# madaq_filter_panel.net
KiCad netlist of a schematic drawn in EAGLE
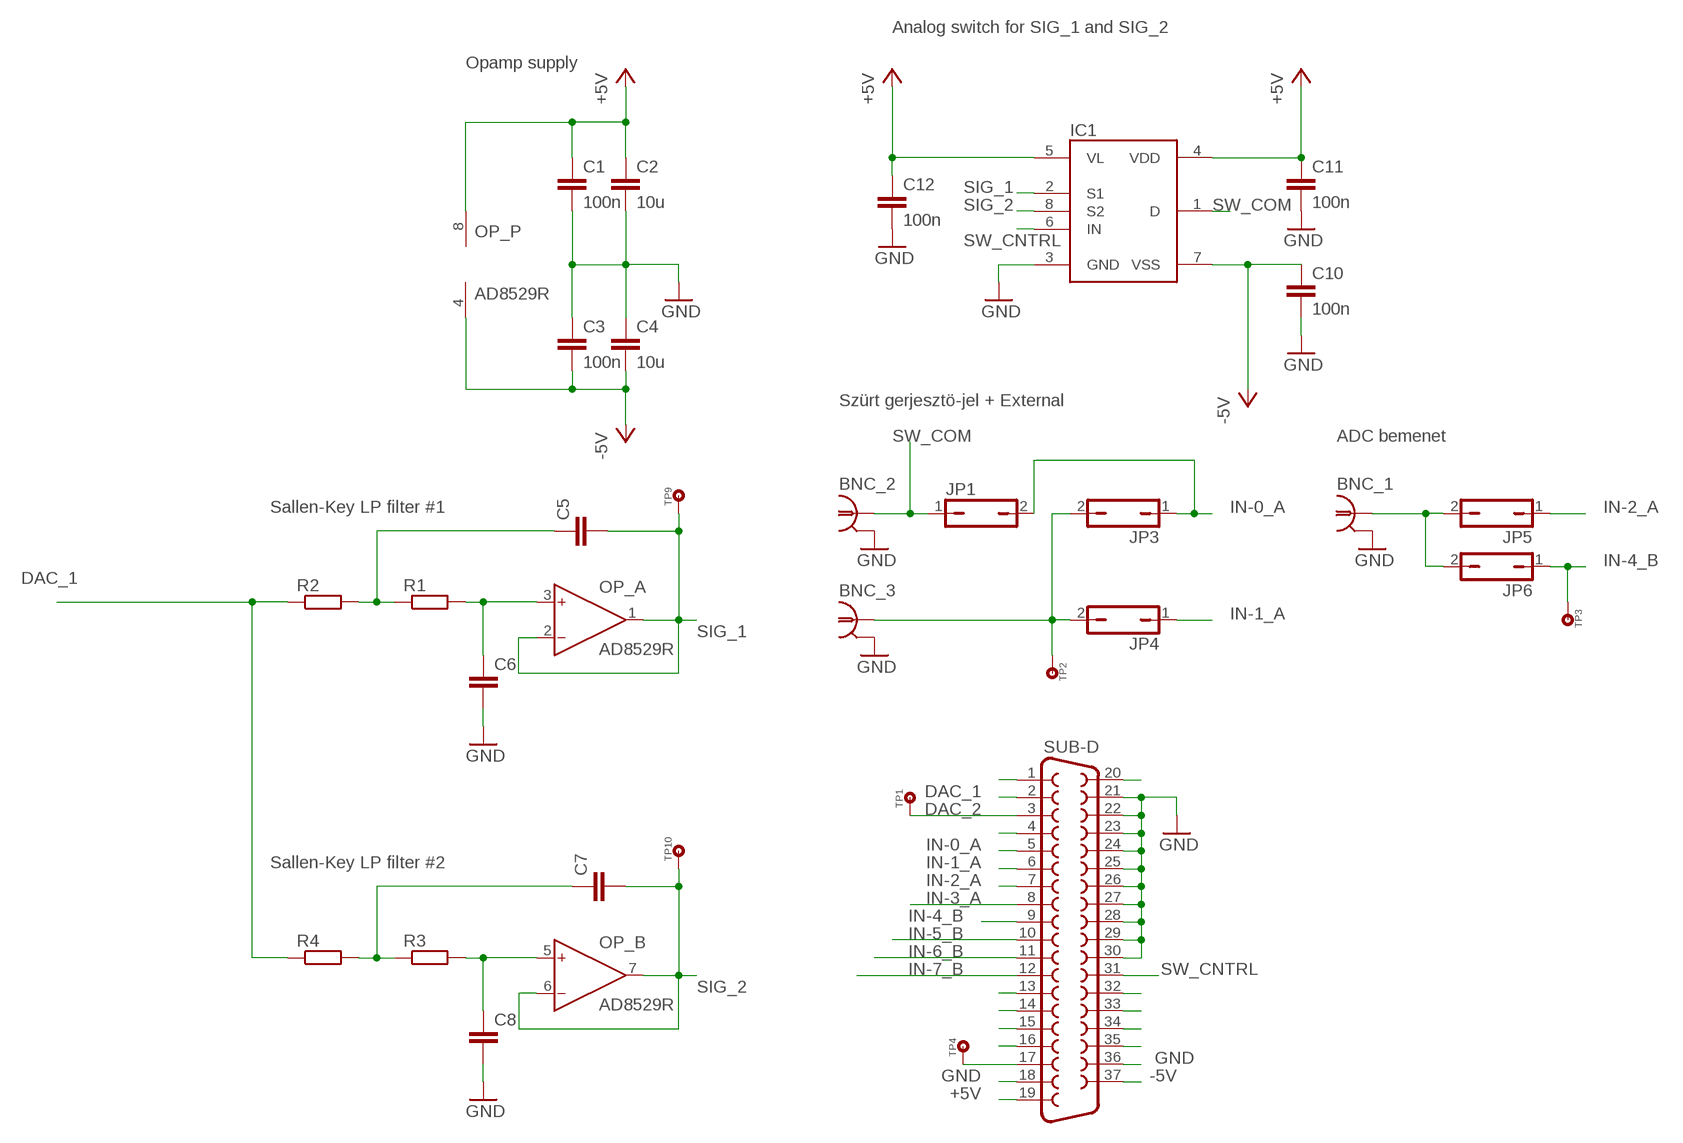
[diagram p0: schematic, sheet 1]

(export (version "E")
  (design (tool "Eeschema 10.0.6"))
  (components
    (comp (ref "BNC_1")
      (value "BNC-ISOL-90I")
      (footprint "eagle-import:BNCPCB90I")
      (libsource (lib "eagle-import") (part "BNC-ISOL-90I"))
    )
    (comp (ref "BNC_2")
      (value "BNC-ISOL-90I")
      (footprint "eagle-import:BNCPCB90I")
      (libsource (lib "eagle-import") (part "BNC-ISOL-90I"))
    )
    (comp (ref "BNC_3")
      (value "BNC-ISOL-90I")
      (footprint "eagle-import:BNCPCB90I")
      (libsource (lib "eagle-import") (part "BNC-ISOL-90I"))
    )
    (comp (ref "C1")
      (value "100n")
      (footprint "eagle-import:C1206")
      (libsource (lib "eagle-import") (part "C1206"))
    )
    (comp (ref "C2")
      (value "10u")
      (footprint "eagle-import:C1206")
      (libsource (lib "eagle-import") (part "C1206"))
    )
    (comp (ref "C3")
      (value "100n")
      (footprint "eagle-import:C1206")
      (libsource (lib "eagle-import") (part "C1206"))
    )
    (comp (ref "C4")
      (value "10u")
      (footprint "eagle-import:C1206")
      (libsource (lib "eagle-import") (part "C1206"))
    )
    (comp (ref "C5")
      (value "C1206")
      (footprint "eagle-import:C1206")
      (libsource (lib "eagle-import") (part "C1206"))
    )
    (comp (ref "C6")
      (value "C1206")
      (footprint "eagle-import:C1206")
      (libsource (lib "eagle-import") (part "C1206"))
    )
    (comp (ref "C7")
      (value "C1206")
      (footprint "eagle-import:C1206")
      (libsource (lib "eagle-import") (part "C1206"))
    )
    (comp (ref "C8")
      (value "C1206")
      (footprint "eagle-import:C1206")
      (libsource (lib "eagle-import") (part "C1206"))
    )
    (comp (ref "C10")
      (value "100n")
      (footprint "eagle-import:C1206")
      (libsource (lib "eagle-import") (part "C1206"))
    )
    (comp (ref "C11")
      (value "100n")
      (footprint "eagle-import:C1206")
      (libsource (lib "eagle-import") (part "C1206"))
    )
    (comp (ref "C12")
      (value "100n")
      (footprint "eagle-import:C1206")
      (libsource (lib "eagle-import") (part "C1206"))
    )
    (comp (ref "IC1")
      (value "ADG419BR")
      (footprint "eagle-import:SO08")
      (libsource (lib "eagle-import") (part "ADG419BR"))
    )
    (comp (ref "JP1")
      (value "JP1Q")
      (footprint "eagle-import:JP1")
      (libsource (lib "eagle-import") (part "JP1Q"))
    )
    (comp (ref "JP3")
      (value "JP1Q")
      (footprint "eagle-import:JP1")
      (libsource (lib "eagle-import") (part "JP1Q"))
    )
    (comp (ref "JP4")
      (value "JP1Q")
      (footprint "eagle-import:JP1")
      (libsource (lib "eagle-import") (part "JP1Q"))
    )
    (comp (ref "JP5")
      (value "JP1Q")
      (footprint "eagle-import:JP1")
      (libsource (lib "eagle-import") (part "JP1Q"))
    )
    (comp (ref "JP6")
      (value "JP1Q")
      (footprint "eagle-import:JP1")
      (libsource (lib "eagle-import") (part "JP1Q"))
    )
    (comp (ref "OP_")
      (value "AD8529R")
      (footprint "eagle-import:SO8")
      (fields (field (name "MF") "ALTERA CORPORATION") (field (name "MPN") "AD8529ARZ"))
      (libsource (lib "eagle-import") (part "AD8529R"))
    )
    (comp (ref "R1")
      (value "R1206")
      (footprint "eagle-import:R1206")
      (libsource (lib "eagle-import") (part "R1206"))
    )
    (comp (ref "R2")
      (value "R1206")
      (footprint "eagle-import:R1206")
      (libsource (lib "eagle-import") (part "R1206"))
    )
    (comp (ref "R3")
      (value "R1206")
      (footprint "eagle-import:R1206")
      (libsource (lib "eagle-import") (part "R1206"))
    )
    (comp (ref "R4")
      (value "R1206")
      (footprint "eagle-import:R1206")
      (libsource (lib "eagle-import") (part "R1206"))
    )
    (comp (ref "SUB-D")
      (value "F37HP")
      (footprint "eagle-import:F37HP")
      (libsource (lib "eagle-import") (part "F37HP"))
    )
    (comp (ref "TP1")
      (value "TP")
      (footprint "eagle-import:JP1")
      (libsource (lib "eagle-import") (part "TP"))
    )
    (comp (ref "TP2")
      (value "TP")
      (footprint "eagle-import:JP1")
      (libsource (lib "eagle-import") (part "TP"))
    )
    (comp (ref "TP3")
      (value "TP")
      (footprint "eagle-import:JP1")
      (libsource (lib "eagle-import") (part "TP"))
    )
    (comp (ref "TP4")
      (value "TP")
      (footprint "eagle-import:JP1")
      (libsource (lib "eagle-import") (part "TP"))
    )
    (comp (ref "TP9")
      (value "TP")
      (footprint "eagle-import:JP1")
      (libsource (lib "eagle-import") (part "TP"))
    )
    (comp (ref "TP10")
      (value "TP")
      (footprint "eagle-import:JP1")
      (libsource (lib "eagle-import") (part "TP"))
    )
  )
  (nets
    (net (code "1") (name "+5V") (class "Default")
      (node (ref "C1") (pin "2") (pinfunction "2_2") (pintype "passive"))
      (node (ref "C11") (pin "2") (pinfunction "2_2") (pintype "passive"))
      (node (ref "C12") (pin "2") (pinfunction "2_2") (pintype "passive"))
      (node (ref "C2") (pin "2") (pinfunction "2_2") (pintype "passive"))
      (node (ref "IC1") (pin "4") (pinfunction "VDD_4") (pintype "power_in"))
      (node (ref "IC1") (pin "5") (pinfunction "VL_5") (pintype "power_in"))
      (node (ref "OP_") (pin "8") (pinfunction "V+_8") (pintype "power_in"))
      (node (ref "SUB-D") (pin "19") (pinfunction "19_19") (pintype "passive"))
    )
    (net (code "2") (name "-5V") (class "Default")
      (node (ref "C10") (pin "2") (pinfunction "2_2") (pintype "passive"))
      (node (ref "C3") (pin "1") (pinfunction "1_1") (pintype "passive"))
      (node (ref "C4") (pin "1") (pinfunction "1_1") (pintype "passive"))
      (node (ref "IC1") (pin "7") (pinfunction "VSS_7") (pintype "power_in"))
      (node (ref "OP_") (pin "4") (pinfunction "V-_4") (pintype "power_in"))
      (node (ref "SUB-D") (pin "37") (pinfunction "37_37") (pintype "passive"))
    )
    (net (code "3") (name "/DAC_1") (class "Default")
      (node (ref "R2") (pin "1") (pinfunction "1_1") (pintype "passive"))
      (node (ref "R4") (pin "1") (pinfunction "1_1") (pintype "passive"))
      (node (ref "SUB-D") (pin "2") (pinfunction "2_2") (pintype "passive"))
    )
    (net (code "4") (name "/DAC_2") (class "Default")
      (node (ref "SUB-D") (pin "3") (pinfunction "3_3") (pintype "passive"))
      (node (ref "TP1") (pin "1") (pinfunction "1_1") (pintype "bidirectional"))
    )
    (net (code "5") (name "/IN-0_A") (class "Default")
      (node (ref "JP1") (pin "2") (pinfunction "2_2") (pintype "passive"))
      (node (ref "JP3") (pin "1") (pinfunction "1_1") (pintype "passive"))
      (node (ref "SUB-D") (pin "5") (pinfunction "5_5") (pintype "passive"))
    )
    (net (code "6") (name "/IN-1_A") (class "Default")
      (node (ref "JP4") (pin "1") (pinfunction "1_1") (pintype "passive"))
      (node (ref "SUB-D") (pin "6") (pinfunction "6_6") (pintype "passive"))
    )
    (net (code "7") (name "/IN-2_A") (class "Default")
      (node (ref "JP5") (pin "1") (pinfunction "1_1") (pintype "passive"))
      (node (ref "SUB-D") (pin "7") (pinfunction "7_7") (pintype "passive"))
    )
    (net (code "8") (name "/IN-3_A") (class "Default")
      (node (ref "SUB-D") (pin "8") (pinfunction "8_8") (pintype "passive"))
    )
    (net (code "9") (name "/IN-4_B") (class "Default")
      (node (ref "JP6") (pin "1") (pinfunction "1_1") (pintype "passive"))
      (node (ref "SUB-D") (pin "9") (pinfunction "9_9") (pintype "passive"))
      (node (ref "TP3") (pin "1") (pinfunction "1_1") (pintype "bidirectional"))
    )
    (net (code "10") (name "/IN-5_B") (class "Default")
      (node (ref "SUB-D") (pin "10") (pinfunction "10_10") (pintype "passive"))
    )
    (net (code "11") (name "/IN-6_B") (class "Default")
      (node (ref "SUB-D") (pin "11") (pinfunction "11_11") (pintype "passive"))
    )
    (net (code "12") (name "/IN-7_B") (class "Default")
      (node (ref "SUB-D") (pin "12") (pinfunction "12_12") (pintype "passive"))
    )
    (net (code "13") (name "/SIG_1") (class "Default")
      (node (ref "C5") (pin "1") (pinfunction "1_1") (pintype "passive"))
      (node (ref "IC1") (pin "2") (pinfunction "S1_2") (pintype "bidirectional"))
      (node (ref "OP_") (pin "1") (pinfunction "OUT_1") (pintype "output"))
      (node (ref "OP_") (pin "2") (pinfunction "IN-_2") (pintype "input"))
      (node (ref "TP9") (pin "1") (pinfunction "1_1") (pintype "bidirectional"))
    )
    (net (code "14") (name "/SIG_2") (class "Default")
      (node (ref "C7") (pin "1") (pinfunction "1_1") (pintype "passive"))
      (node (ref "IC1") (pin "8") (pinfunction "S2_8") (pintype "bidirectional"))
      (node (ref "OP_") (pin "6") (pinfunction "IN-_6") (pintype "input"))
      (node (ref "OP_") (pin "7") (pinfunction "OUT_7") (pintype "output"))
      (node (ref "TP10") (pin "1") (pinfunction "1_1") (pintype "bidirectional"))
    )
    (net (code "15") (name "/SW_CNTRL") (class "Default")
      (node (ref "IC1") (pin "6") (pinfunction "IN_6") (pintype "input"))
      (node (ref "SUB-D") (pin "31") (pinfunction "31_31") (pintype "passive"))
    )
    (net (code "16") (name "/SW_COM") (class "Default")
      (node (ref "BNC_2") (pin "SIGNAL") (pinfunction "SIGNAL_SIGNAL") (pintype "passive"))
      (node (ref "IC1") (pin "1") (pinfunction "D_1") (pintype "bidirectional"))
      (node (ref "JP1") (pin "1") (pinfunction "1_1") (pintype "passive"))
    )
    (net (code "17") (name "GND") (class "Default")
      (node (ref "BNC_1") (pin "SHIELD") (pinfunction "SHIELD_SHIELD") (pintype "passive"))
      (node (ref "BNC_2") (pin "SHIELD") (pinfunction "SHIELD_SHIELD") (pintype "passive"))
      (node (ref "BNC_3") (pin "SHIELD") (pinfunction "SHIELD_SHIELD") (pintype "passive"))
      (node (ref "C1") (pin "1") (pinfunction "1_1") (pintype "passive"))
      (node (ref "C10") (pin "1") (pinfunction "1_1") (pintype "passive"))
      (node (ref "C11") (pin "1") (pinfunction "1_1") (pintype "passive"))
      (node (ref "C12") (pin "1") (pinfunction "1_1") (pintype "passive"))
      (node (ref "C2") (pin "1") (pinfunction "1_1") (pintype "passive"))
      (node (ref "C3") (pin "2") (pinfunction "2_2") (pintype "passive"))
      (node (ref "C4") (pin "2") (pinfunction "2_2") (pintype "passive"))
      (node (ref "C6") (pin "1") (pinfunction "1_1") (pintype "passive"))
      (node (ref "C8") (pin "1") (pinfunction "1_1") (pintype "passive"))
      (node (ref "IC1") (pin "3") (pinfunction "GND_3") (pintype "power_in"))
      (node (ref "SUB-D") (pin "18") (pinfunction "18_18") (pintype "passive"))
      (node (ref "SUB-D") (pin "21") (pinfunction "21_21") (pintype "passive"))
      (node (ref "SUB-D") (pin "22") (pinfunction "22_22") (pintype "passive"))
      (node (ref "SUB-D") (pin "23") (pinfunction "23_23") (pintype "passive"))
      (node (ref "SUB-D") (pin "24") (pinfunction "24_24") (pintype "passive"))
      (node (ref "SUB-D") (pin "25") (pinfunction "25_25") (pintype "passive"))
      (node (ref "SUB-D") (pin "26") (pinfunction "26_26") (pintype "passive"))
      (node (ref "SUB-D") (pin "27") (pinfunction "27_27") (pintype "passive"))
      (node (ref "SUB-D") (pin "28") (pinfunction "28_28") (pintype "passive"))
      (node (ref "SUB-D") (pin "29") (pinfunction "29_29") (pintype "passive"))
      (node (ref "SUB-D") (pin "30") (pinfunction "30_30") (pintype "passive"))
      (node (ref "SUB-D") (pin "36") (pinfunction "36_36") (pintype "passive"))
    )
    (net (code "18") (name "Net-(BNC_1-PadSIGNAL)") (class "Default")
      (node (ref "BNC_1") (pin "SIGNAL") (pinfunction "SIGNAL_SIGNAL") (pintype "passive"))
      (node (ref "JP5") (pin "2") (pinfunction "2_2") (pintype "passive"))
      (node (ref "JP6") (pin "2") (pinfunction "2_2") (pintype "passive"))
    )
    (net (code "19") (name "Net-(BNC_3-PadSIGNAL)") (class "Default")
      (node (ref "BNC_3") (pin "SIGNAL") (pinfunction "SIGNAL_SIGNAL") (pintype "passive"))
      (node (ref "JP3") (pin "2") (pinfunction "2_2") (pintype "passive"))
      (node (ref "JP4") (pin "2") (pinfunction "2_2") (pintype "passive"))
      (node (ref "TP2") (pin "1") (pinfunction "1_1") (pintype "bidirectional"))
    )
    (net (code "20") (name "Net-(C5-Pad2)") (class "Default")
      (node (ref "C5") (pin "2") (pinfunction "2_2") (pintype "passive"))
      (node (ref "R1") (pin "1") (pinfunction "1_1") (pintype "passive"))
      (node (ref "R2") (pin "2") (pinfunction "2_2") (pintype "passive"))
    )
    (net (code "21") (name "Net-(C7-Pad2)") (class "Default")
      (node (ref "C7") (pin "2") (pinfunction "2_2") (pintype "passive"))
      (node (ref "R3") (pin "1") (pinfunction "1_1") (pintype "passive"))
      (node (ref "R4") (pin "2") (pinfunction "2_2") (pintype "passive"))
    )
    (net (code "22") (name "Net-(OP_A-IN+)") (class "Default")
      (node (ref "C6") (pin "2") (pinfunction "2_2") (pintype "passive"))
      (node (ref "OP_") (pin "3") (pinfunction "IN+_3") (pintype "input"))
      (node (ref "R1") (pin "2") (pinfunction "2_2") (pintype "passive"))
    )
    (net (code "23") (name "Net-(OP_B-IN+)") (class "Default")
      (node (ref "C8") (pin "2") (pinfunction "2_2") (pintype "passive"))
      (node (ref "OP_") (pin "5") (pinfunction "IN+_5") (pintype "input"))
      (node (ref "R3") (pin "2") (pinfunction "2_2") (pintype "passive"))
    )
    (net (code "24") (name "Net-(SUB-D-Pad17)") (class "Default")
      (node (ref "SUB-D") (pin "17") (pinfunction "17_17") (pintype "passive"))
      (node (ref "TP4") (pin "1") (pinfunction "1_1") (pintype "bidirectional"))
    )
    (net (code "25") (name "unconnected-(SUB-D-Pad1)") (class "Default")
      (node (ref "SUB-D") (pin "1") (pinfunction "1_1") (pintype "passive"))
    )
    (net (code "26") (name "unconnected-(SUB-D-Pad4)") (class "Default")
      (node (ref "SUB-D") (pin "4") (pinfunction "4_4") (pintype "passive"))
    )
    (net (code "27") (name "unconnected-(SUB-D-Pad13)") (class "Default")
      (node (ref "SUB-D") (pin "13") (pinfunction "13_13") (pintype "passive"))
    )
    (net (code "28") (name "unconnected-(SUB-D-Pad14)") (class "Default")
      (node (ref "SUB-D") (pin "14") (pinfunction "14_14") (pintype "passive"))
    )
    (net (code "29") (name "unconnected-(SUB-D-Pad15)") (class "Default")
      (node (ref "SUB-D") (pin "15") (pinfunction "15_15") (pintype "passive"))
    )
    (net (code "30") (name "unconnected-(SUB-D-Pad16)") (class "Default")
      (node (ref "SUB-D") (pin "16") (pinfunction "16_16") (pintype "passive"))
    )
    (net (code "31") (name "unconnected-(SUB-D-Pad20)") (class "Default")
      (node (ref "SUB-D") (pin "20") (pinfunction "20_20") (pintype "passive"))
    )
    (net (code "32") (name "unconnected-(SUB-D-Pad32)") (class "Default")
      (node (ref "SUB-D") (pin "32") (pinfunction "32_32") (pintype "passive"))
    )
    (net (code "33") (name "unconnected-(SUB-D-Pad33)") (class "Default")
      (node (ref "SUB-D") (pin "33") (pinfunction "33_33") (pintype "passive"))
    )
    (net (code "34") (name "unconnected-(SUB-D-Pad34)") (class "Default")
      (node (ref "SUB-D") (pin "34") (pinfunction "34_34") (pintype "passive"))
    )
    (net (code "35") (name "unconnected-(SUB-D-Pad35)") (class "Default")
      (node (ref "SUB-D") (pin "35") (pinfunction "35_35") (pintype "passive"))
    )
  )
)
